# Pince.net
KiCad netlist of a schematic drawn in Altium Designer
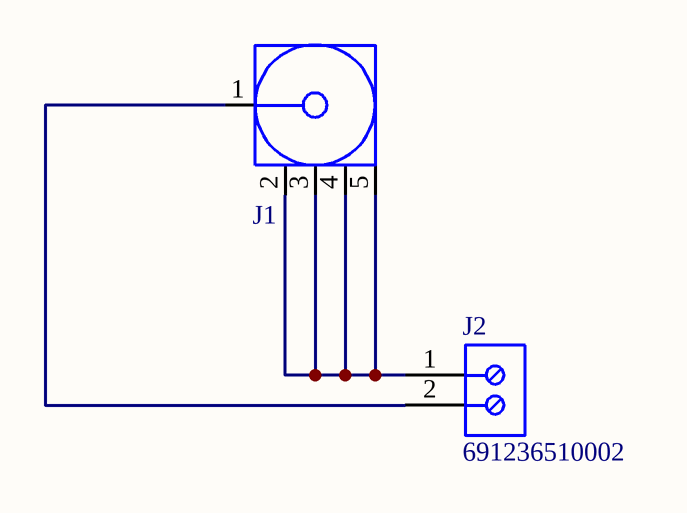
[diagram p0: Pince.SchDoc]

(export (version "E")
  (design (tool "Eeschema 10.0.6"))
  (components
    (comp (ref "J1")
      (value "60411042241501")
      (footprint "60411042241501")
      (description "WR-NTYPE N Type PCB Connector, Right Angle Jack, DC~4GHz, 50Ohm")
      (fields (field (name "MANUFACTURER") "Wurth Elektronik"))
      (libsource (lib "Altium_WR-NTYPE (rev22a)") (part "60411042241501"))
    )
    (comp (ref "J2")
      (value "691236510002")
      (footprint "691236510002")
      (description "WR-TBL Serie 2365 Horizontal Entry, Rising Cage Clamp, pitch 5.08mm, 2p")
      (fields (field (name "PUBLISHER") "Wurth Elektronik"))
      (libsource (lib "WR-TBL (rev19a)") (part "691236510002"))
    )
  )
  (nets
    (net (code "1") (name "Net-(J1-GND-Pad2)") (class "Default")
      (node (ref "J1") (pin "2") (pinfunction "GND_2") (pintype "passive"))
      (node (ref "J1") (pin "3") (pinfunction "GND_3") (pintype "passive"))
      (node (ref "J1") (pin "4") (pinfunction "GND_4") (pintype "passive"))
      (node (ref "J1") (pin "5") (pinfunction "GND_5") (pintype "passive"))
      (node (ref "J2") (pin "1") (pinfunction "1_1") (pintype "passive"))
    )
    (net (code "2") (name "Net-(J1-Signal)") (class "Default")
      (node (ref "J1") (pin "1") (pinfunction "Signal_1") (pintype "passive"))
      (node (ref "J2") (pin "2") (pinfunction "2_2") (pintype "passive"))
    )
  )
)
